# CommunicationBoard.net
KiCad netlist of a schematic drawn in EAGLE
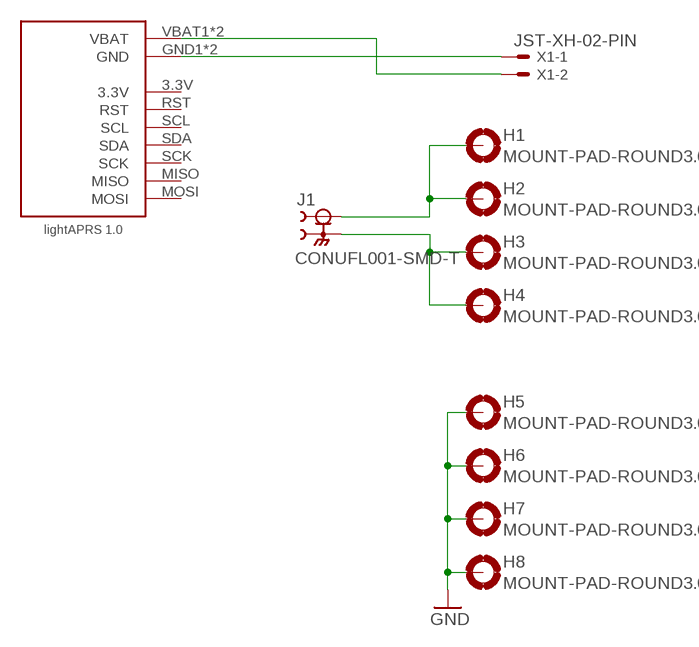
[diagram p0: schematic, sheet 1]

(export (version "E")
  (design (tool "Eeschema 10.0.6"))
  (components
    (comp (ref "H1")
      (value "MOUNT-PAD-ROUND3.0")
      (footprint "eagle-import:3,0-PAD")
      (libsource (lib "eagle-import") (part "MOUNT-PAD-ROUND3.0"))
    )
    (comp (ref "H2")
      (value "MOUNT-PAD-ROUND3.0")
      (footprint "eagle-import:3,0-PAD")
      (libsource (lib "eagle-import") (part "MOUNT-PAD-ROUND3.0"))
    )
    (comp (ref "H3")
      (value "MOUNT-PAD-ROUND3.0")
      (footprint "eagle-import:3,0-PAD")
      (libsource (lib "eagle-import") (part "MOUNT-PAD-ROUND3.0"))
    )
    (comp (ref "H4")
      (value "MOUNT-PAD-ROUND3.0")
      (footprint "eagle-import:3,0-PAD")
      (libsource (lib "eagle-import") (part "MOUNT-PAD-ROUND3.0"))
    )
    (comp (ref "H5")
      (value "MOUNT-PAD-ROUND3.0")
      (footprint "eagle-import:3,0-PAD")
      (libsource (lib "eagle-import") (part "MOUNT-PAD-ROUND3.0"))
    )
    (comp (ref "H6")
      (value "MOUNT-PAD-ROUND3.0")
      (footprint "eagle-import:3,0-PAD")
      (libsource (lib "eagle-import") (part "MOUNT-PAD-ROUND3.0"))
    )
    (comp (ref "H7")
      (value "MOUNT-PAD-ROUND3.0")
      (footprint "eagle-import:3,0-PAD")
      (libsource (lib "eagle-import") (part "MOUNT-PAD-ROUND3.0"))
    )
    (comp (ref "H8")
      (value "MOUNT-PAD-ROUND3.0")
      (footprint "eagle-import:3,0-PAD")
      (libsource (lib "eagle-import") (part "MOUNT-PAD-ROUND3.0"))
    )
    (comp (ref "J1")
      (value "CONUFL001-SMD-T")
      (footprint "eagle-import:LINX_CONUFL001-SMD-T")
      (fields (field (name "MF") "Linx Technologies") (field (name "MP") "CONUFL001-SMD"))
      (libsource (lib "eagle-import") (part "CONUFL001-SMD-T"))
    )
    (comp (ref "U$1")
      (value "LIGHTAPRS")
      (footprint "eagle-import:LIGHTAPRS")
      (libsource (lib "eagle-import") (part "LIGHTAPRS"))
    )
    (comp (ref "X1")
      (value "JST-XH-02-PIN")
      (footprint "eagle-import:JST-XH_S2B")
      (libsource (lib "eagle-import") (part "JST-XH-02-PIN"))
    )
  )
  (nets
    (net (code "1") (name "GND") (class "Default")
      (node (ref "H5") (pin "B3,0") (pinfunction "MOUNT_B3,0") (pintype "passive"))
      (node (ref "H6") (pin "B3,0") (pinfunction "MOUNT_B3,0") (pintype "passive"))
      (node (ref "H7") (pin "B3,0") (pinfunction "MOUNT_B3,0") (pintype "passive"))
      (node (ref "H8") (pin "B3,0") (pinfunction "MOUNT_B3,0") (pintype "passive"))
      (node (ref "U$1") (pin "GND1") (pinfunction "GND_GND1") (pintype "bidirectional"))
      (node (ref "U$1") (pin "GND2") (pinfunction "GND_GND2") (pintype "bidirectional"))
      (node (ref "X1") (pin "PIN1") (pinfunction "S_PIN1") (pintype "passive"))
    )
    (net (code "2") (name "Net-(H1-MOUNT)") (class "Default")
      (node (ref "H1") (pin "B3,0") (pinfunction "MOUNT_B3,0") (pintype "passive"))
      (node (ref "H2") (pin "B3,0") (pinfunction "MOUNT_B3,0") (pintype "passive"))
      (node (ref "J1") (pin "1") (pinfunction "1_1") (pintype "passive"))
    )
    (net (code "3") (name "Net-(H3-MOUNT)") (class "Default")
      (node (ref "H3") (pin "B3,0") (pinfunction "MOUNT_B3,0") (pintype "passive"))
      (node (ref "H4") (pin "B3,0") (pinfunction "MOUNT_B3,0") (pintype "passive"))
      (node (ref "J1") (pin "2") (pinfunction "2_2") (pintype "passive"))
      (node (ref "J1") (pin "3") (pinfunction "2_3") (pintype "passive"))
    )
    (net (code "4") (name "Net-(X1B-S)") (class "Default")
      (node (ref "U$1") (pin "VBAT1") (pinfunction "VBAT_VBAT1") (pintype "bidirectional"))
      (node (ref "U$1") (pin "VBAT2") (pinfunction "VBAT_VBAT2") (pintype "bidirectional"))
      (node (ref "X1") (pin "PIN2") (pinfunction "S_PIN2") (pintype "passive"))
    )
    (net (code "5") (name "unconnected-(U$1-Pad3.3V)") (class "Default")
      (node (ref "U$1") (pin "3.3V") (pinfunction "3.3V_3.3V") (pintype "bidirectional"))
    )
    (net (code "6") (name "unconnected-(U$1-PadMISO)") (class "Default")
      (node (ref "U$1") (pin "MISO") (pinfunction "MISO_MISO") (pintype "bidirectional"))
    )
    (net (code "7") (name "unconnected-(U$1-PadMOSI)") (class "Default")
      (node (ref "U$1") (pin "MOSI") (pinfunction "MOSI_MOSI") (pintype "bidirectional"))
    )
    (net (code "8") (name "unconnected-(U$1-PadRST)") (class "Default")
      (node (ref "U$1") (pin "RST") (pinfunction "RST_RST") (pintype "bidirectional"))
    )
    (net (code "9") (name "unconnected-(U$1-PadSCK)") (class "Default")
      (node (ref "U$1") (pin "SCK") (pinfunction "SCK_SCK") (pintype "bidirectional"))
    )
    (net (code "10") (name "unconnected-(U$1-PadSCL)") (class "Default")
      (node (ref "U$1") (pin "SCL") (pinfunction "SCL_SCL") (pintype "bidirectional"))
    )
    (net (code "11") (name "unconnected-(U$1-PadSDA)") (class "Default")
      (node (ref "U$1") (pin "SDA") (pinfunction "SDA_SDA") (pintype "bidirectional"))
    )
  )
)
